# schematic.net
KiCad netlist of a schematic drawn in Altium Designer
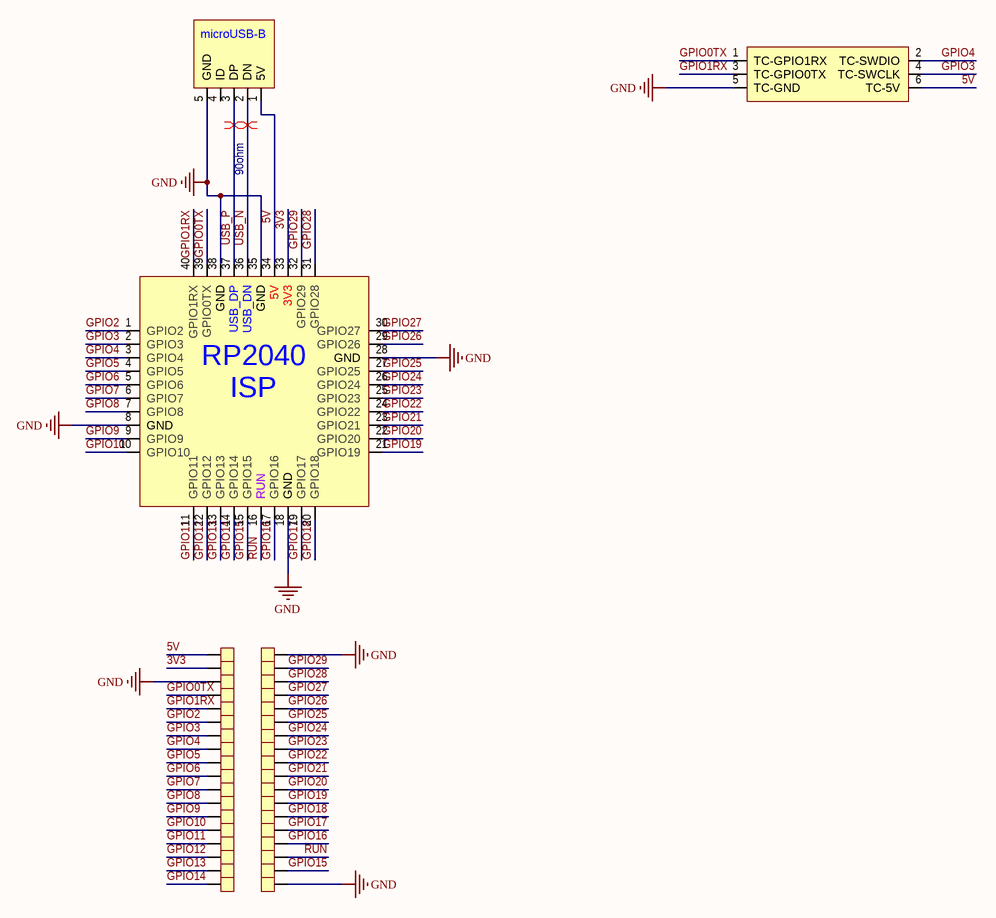
[diagram p0: schematic.SchDoc]

(export (version "E")
  (design (tool "Eeschema 10.0.6"))
  (components
    (comp (ref "J2")
      (value "BOX_HEADER")
      (footprint "BOX_HEADER")
      (description "Connector Header Through Hole 6 position 0.100\" (2.54mm)")
      (libsource (lib "sch_library") (part "BOX_HEADER"))
    )
    (comp (ref "J4")
      (value "MICRO_USB_B")
      (footprint "MICRO_USB_B")
      (description "USB - micro B Receptacle Connector 5 Position Board Edge, Cutout; Surface Mount, Right Angle")
      (libsource (lib "sch_library") (part "MICRO_USB_B"))
    )
    (comp (ref "J5")
      (value "HEADER")
      (footprint "Header_1x6")
      (libsource (lib "sch_library") (part "HEADER"))
    )
    (comp (ref "J6")
      (value "HEADER")
      (footprint "Header_1x6")
      (libsource (lib "sch_library") (part "HEADER"))
    )
    (comp (ref "J7") (value "HEADER") (footprint "Header_1x6") (libsource (lib "") (part "HEADER_1")))
    (comp (ref "J8")
      (value "HEADER")
      (footprint "Header_1x6")
      (libsource (lib "sch_library") (part "HEADER"))
    )
    (comp (ref "J9") (value "HEADER") (footprint "Header_1x6") (libsource (lib "") (part "HEADER_1")))
    (comp (ref "J10") (value "HEADER") (footprint "Header_1x6") (libsource (lib "") (part "HEADER_1")))
    (comp (ref "U1")
      (value "RP2040_ISP_STAMP")
      (footprint "RP2040_ISP_STAMP")
      (libsource (lib "sch_library") (part "RP2040_ISP_STAMP"))
    )
  )
  (nets
    (net (code "1") (name "/3V3") (class "Default")
      (node (ref "J5") (pin "2") (pinfunction "2_2") (pintype "passive"))
      (node (ref "U1") (pin "33") (pinfunction "3V3_33") (pintype "passive"))
    )
    (net (code "2") (name "/5V") (class "Default")
      (node (ref "J2") (pin "6") (pinfunction "TC-5V_6") (pintype "passive"))
      (node (ref "J4") (pin "1") (pinfunction "5V_1") (pintype "passive"))
      (node (ref "J5") (pin "1") (pinfunction "1_1") (pintype "passive"))
      (node (ref "U1") (pin "34") (pinfunction "5V_34") (pintype "passive"))
    )
    (net (code "3") (name "/GPIO0TX") (class "Default")
      (node (ref "J2") (pin "1") (pinfunction "TC-GPIO1RX_1") (pintype "passive"))
      (node (ref "J5") (pin "4") (pinfunction "4_4") (pintype "passive"))
      (node (ref "U1") (pin "39") (pinfunction "GPIO0TX_39") (pintype "passive"))
    )
    (net (code "4") (name "/GPIO1RX") (class "Default")
      (node (ref "J2") (pin "3") (pinfunction "TC-GPIO0TX_3") (pintype "passive"))
      (node (ref "J5") (pin "5") (pinfunction "5_5") (pintype "passive"))
      (node (ref "U1") (pin "40") (pinfunction "GPIO1RX_40") (pintype "passive"))
    )
    (net (code "5") (name "/GPIO2") (class "Default")
      (node (ref "J5") (pin "6") (pinfunction "6_6") (pintype "passive"))
      (node (ref "U1") (pin "1") (pinfunction "GPIO2_1") (pintype "passive"))
    )
    (net (code "6") (name "/GPIO3") (class "Default")
      (node (ref "J2") (pin "4") (pinfunction "TC-SWCLK_4") (pintype "passive"))
      (node (ref "J6") (pin "1") (pinfunction "1_1") (pintype "passive"))
      (node (ref "U1") (pin "2") (pinfunction "GPIO3_2") (pintype "passive"))
    )
    (net (code "7") (name "/GPIO4") (class "Default")
      (node (ref "J2") (pin "2") (pinfunction "TC-SWDIO_2") (pintype "passive"))
      (node (ref "J6") (pin "2") (pinfunction "2_2") (pintype "passive"))
      (node (ref "U1") (pin "3") (pinfunction "GPIO4_3") (pintype "passive"))
    )
    (net (code "8") (name "/GPIO5") (class "Default")
      (node (ref "J6") (pin "3") (pinfunction "3_3") (pintype "passive"))
      (node (ref "U1") (pin "4") (pinfunction "GPIO5_4") (pintype "passive"))
    )
    (net (code "9") (name "/GPIO6") (class "Default")
      (node (ref "J6") (pin "4") (pinfunction "4_4") (pintype "passive"))
      (node (ref "U1") (pin "5") (pinfunction "GPIO6_5") (pintype "passive"))
    )
    (net (code "10") (name "/GPIO7") (class "Default")
      (node (ref "J6") (pin "5") (pinfunction "5_5") (pintype "passive"))
      (node (ref "U1") (pin "6") (pinfunction "GPIO7_6") (pintype "passive"))
    )
    (net (code "11") (name "/GPIO8") (class "Default")
      (node (ref "J6") (pin "6") (pinfunction "6_6") (pintype "passive"))
      (node (ref "U1") (pin "7") (pinfunction "GPIO8_7") (pintype "passive"))
    )
    (net (code "12") (name "/GPIO9") (class "Default")
      (node (ref "J8") (pin "1") (pinfunction "1_1") (pintype "passive"))
      (node (ref "U1") (pin "9") (pinfunction "GPIO9_9") (pintype "passive"))
    )
    (net (code "13") (name "/GPIO10") (class "Default")
      (node (ref "J8") (pin "2") (pinfunction "2_2") (pintype "passive"))
      (node (ref "U1") (pin "10") (pinfunction "GPIO10_10") (pintype "passive"))
    )
    (net (code "14") (name "/GPIO11") (class "Default")
      (node (ref "J8") (pin "3") (pinfunction "3_3") (pintype "passive"))
      (node (ref "U1") (pin "11") (pinfunction "GPIO11_11") (pintype "passive"))
    )
    (net (code "15") (name "/GPIO12") (class "Default")
      (node (ref "J8") (pin "4") (pinfunction "4_4") (pintype "passive"))
      (node (ref "U1") (pin "12") (pinfunction "GPIO12_12") (pintype "passive"))
    )
    (net (code "16") (name "/GPIO13") (class "Default")
      (node (ref "J8") (pin "5") (pinfunction "5_5") (pintype "passive"))
      (node (ref "U1") (pin "13") (pinfunction "GPIO13_13") (pintype "passive"))
    )
    (net (code "17") (name "/GPIO14") (class "Default")
      (node (ref "J8") (pin "6") (pinfunction "6_6") (pintype "passive"))
      (node (ref "U1") (pin "14") (pinfunction "GPIO14_14") (pintype "passive"))
    )
    (net (code "18") (name "/GPIO15") (class "Default")
      (node (ref "J10") (pin "5") (pinfunction "5_5") (pintype "passive"))
      (node (ref "U1") (pin "15") (pinfunction "GPIO15_15") (pintype "passive"))
    )
    (net (code "19") (name "/GPIO16") (class "Default")
      (node (ref "J10") (pin "3") (pinfunction "3_3") (pintype "passive"))
      (node (ref "U1") (pin "17") (pinfunction "GPIO16_17") (pintype "passive"))
    )
    (net (code "20") (name "/GPIO17") (class "Default")
      (node (ref "J10") (pin "2") (pinfunction "2_2") (pintype "passive"))
      (node (ref "U1") (pin "19") (pinfunction "GPIO17_19") (pintype "passive"))
    )
    (net (code "21") (name "/GPIO18") (class "Default")
      (node (ref "J10") (pin "1") (pinfunction "1_1") (pintype "passive"))
      (node (ref "U1") (pin "20") (pinfunction "GPIO18_20") (pintype "passive"))
    )
    (net (code "22") (name "/GPIO19") (class "Default")
      (node (ref "J9") (pin "6") (pinfunction "6_6") (pintype "passive"))
      (node (ref "U1") (pin "21") (pinfunction "GPIO19_21") (pintype "passive"))
    )
    (net (code "23") (name "/GPIO20") (class "Default")
      (node (ref "J9") (pin "5") (pinfunction "5_5") (pintype "passive"))
      (node (ref "U1") (pin "22") (pinfunction "GPIO20_22") (pintype "passive"))
    )
    (net (code "24") (name "/GPIO21") (class "Default")
      (node (ref "J9") (pin "4") (pinfunction "4_4") (pintype "passive"))
      (node (ref "U1") (pin "23") (pinfunction "GPIO21_23") (pintype "passive"))
    )
    (net (code "25") (name "/GPIO22") (class "Default")
      (node (ref "J9") (pin "3") (pinfunction "3_3") (pintype "passive"))
      (node (ref "U1") (pin "24") (pinfunction "GPIO22_24") (pintype "passive"))
    )
    (net (code "26") (name "/GPIO23") (class "Default")
      (node (ref "J9") (pin "2") (pinfunction "2_2") (pintype "passive"))
      (node (ref "U1") (pin "25") (pinfunction "GPIO23_25") (pintype "passive"))
    )
    (net (code "27") (name "/GPIO24") (class "Default")
      (node (ref "J9") (pin "1") (pinfunction "1_1") (pintype "passive"))
      (node (ref "U1") (pin "26") (pinfunction "GPIO24_26") (pintype "passive"))
    )
    (net (code "28") (name "/GPIO25") (class "Default")
      (node (ref "J7") (pin "6") (pinfunction "6_6") (pintype "passive"))
      (node (ref "U1") (pin "27") (pinfunction "GPIO25_27") (pintype "passive"))
    )
    (net (code "29") (name "/GPIO26") (class "Default")
      (node (ref "J7") (pin "5") (pinfunction "5_5") (pintype "passive"))
      (node (ref "U1") (pin "29") (pinfunction "GPIO26_29") (pintype "passive"))
    )
    (net (code "30") (name "/GPIO27") (class "Default")
      (node (ref "J7") (pin "4") (pinfunction "4_4") (pintype "passive"))
      (node (ref "U1") (pin "30") (pinfunction "GPIO27_30") (pintype "passive"))
    )
    (net (code "31") (name "/GPIO28") (class "Default")
      (node (ref "J7") (pin "3") (pinfunction "3_3") (pintype "passive"))
      (node (ref "U1") (pin "31") (pinfunction "GPIO28_31") (pintype "passive"))
    )
    (net (code "32") (name "/GPIO29") (class "Default")
      (node (ref "J7") (pin "2") (pinfunction "2_2") (pintype "passive"))
      (node (ref "U1") (pin "32") (pinfunction "GPIO29_32") (pintype "passive"))
    )
    (net (code "33") (name "/RUN") (class "Default")
      (node (ref "J10") (pin "4") (pinfunction "4_4") (pintype "passive"))
      (node (ref "U1") (pin "16") (pinfunction "RUN_16") (pintype "passive"))
    )
    (net (code "34") (name "/USB_N") (class "Default")
      (node (ref "J4") (pin "2") (pinfunction "DN_2") (pintype "passive"))
      (node (ref "U1") (pin "36") (pinfunction "USB_DN_36") (pintype "passive"))
    )
    (net (code "35") (name "/USB_P") (class "Default")
      (node (ref "J4") (pin "3") (pinfunction "DP_3") (pintype "passive"))
      (node (ref "U1") (pin "37") (pinfunction "USB_DP_37") (pintype "passive"))
    )
    (net (code "36") (name "GND") (class "Default")
      (node (ref "J10") (pin "6") (pinfunction "6_6") (pintype "passive"))
      (node (ref "J2") (pin "5") (pinfunction "TC-GND_5") (pintype "passive"))
      (node (ref "J4") (pin "5") (pinfunction "GND_5") (pintype "passive"))
      (node (ref "J5") (pin "3") (pinfunction "3_3") (pintype "passive"))
      (node (ref "J7") (pin "1") (pinfunction "1_1") (pintype "passive"))
      (node (ref "U1") (pin "18") (pinfunction "GND_18") (pintype "passive"))
      (node (ref "U1") (pin "28") (pinfunction "GND_28") (pintype "passive"))
      (node (ref "U1") (pin "35") (pinfunction "GND_35") (pintype "passive"))
      (node (ref "U1") (pin "38") (pinfunction "GND_38") (pintype "passive"))
      (node (ref "U1") (pin "8") (pinfunction "GND_8") (pintype "passive"))
    )
    (net (code "37") (name "unconnected-(J4-ID-Pad4)") (class "Default")
      (node (ref "J4") (pin "4") (pinfunction "ID_4") (pintype "passive"))
    )
  )
)
